# 80352201_Main_v4_1_1.net
KiCad netlist of a schematic drawn in Altium Designer
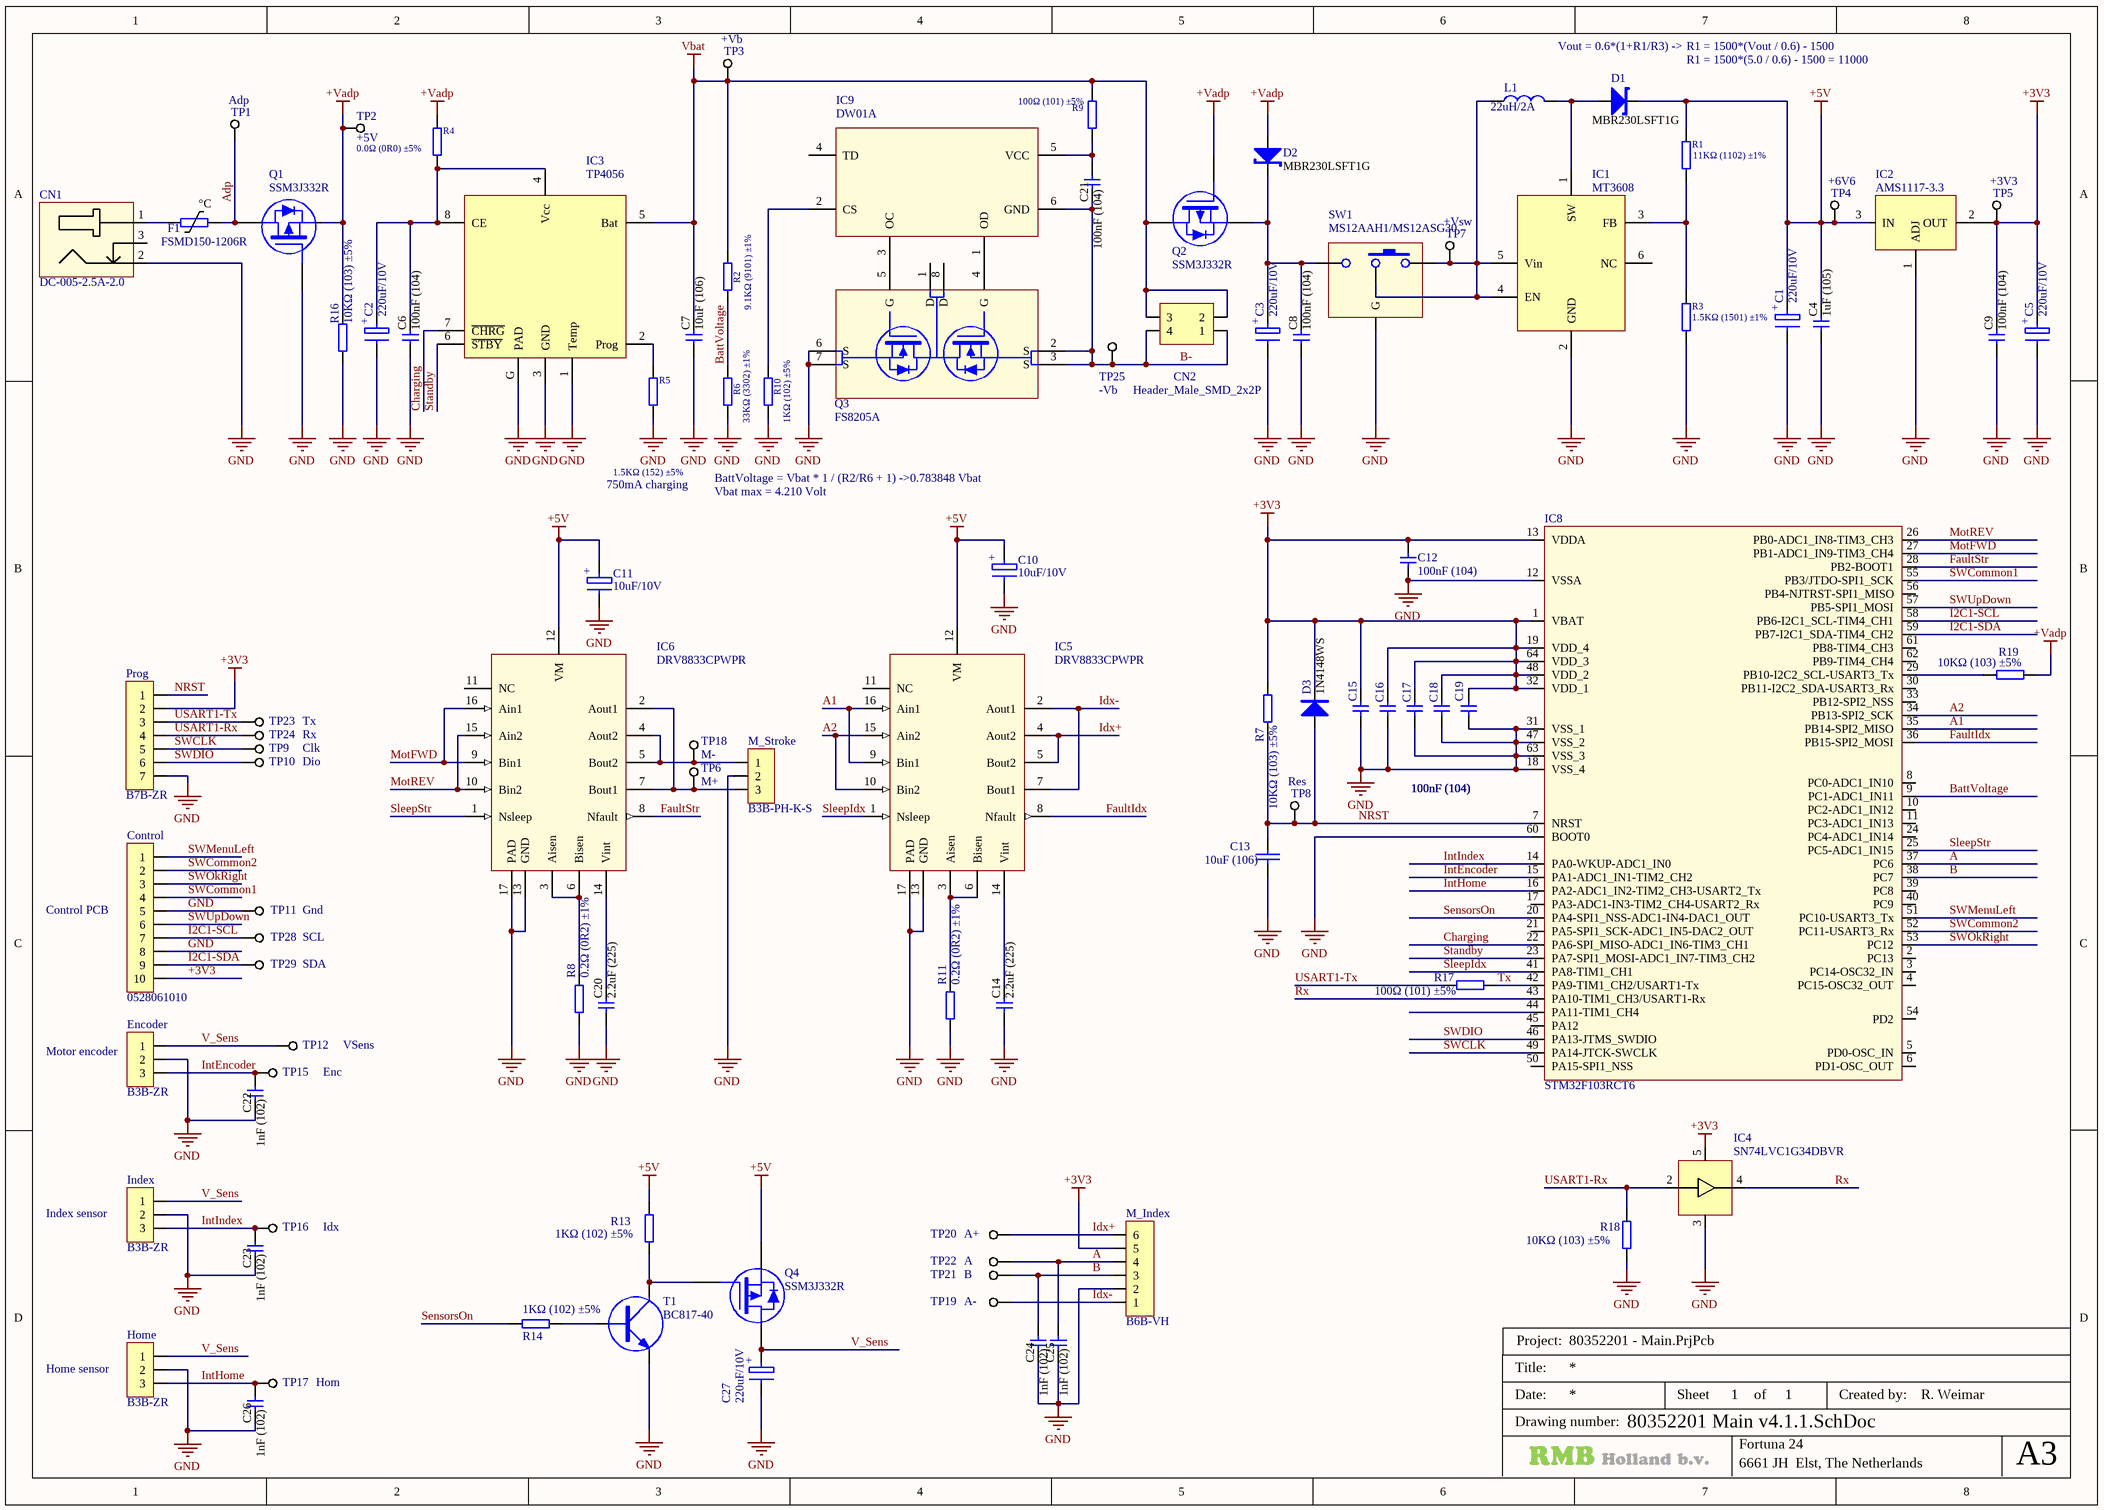
[diagram p0: 80352201 Main v4.1.1.SchDoc]

(export (version "E")
  (design (tool "Eeschema 10.0.6"))
  (components
    (comp (ref "C1")
      (value "220uF/10V")
      (footprint "C/CAP_POL_6032-28")
      (description "CapacitorPol")
      (libsource (lib "ReneWeimar") (part "C/CAP_Pol"))
    )
    (comp (ref "C2")
      (value "220uF/10V")
      (footprint "C/CAP_POL_6032-28")
      (description "CapacitorPol")
      (libsource (lib "ReneWeimar") (part "C/CAP_Pol"))
    )
    (comp (ref "C3")
      (value "220uF/10V")
      (footprint "C/CAP_POL_6032-28")
      (description "CapacitorPol")
      (libsource (lib "ReneWeimar") (part "C/CAP_Pol"))
    )
    (comp (ref "C4")
      (value "1uF (105)")
      (footprint "C/0603/H")
      (description "Capacitor")
      (libsource (lib "ReneWeimar") (part "CAP"))
    )
    (comp (ref "C5")
      (value "220uF/10V")
      (footprint "C/CAP_POL_6032-28")
      (description "CapacitorPol")
      (libsource (lib "ReneWeimar") (part "C/CAP_Pol"))
    )
    (comp (ref "C6")
      (value "100nF (104)")
      (footprint "C/0603/H")
      (description "Capacitor")
      (libsource (lib "ReneWeimar") (part "CAP"))
    )
    (comp (ref "C7")
      (value "10uF (106)")
      (footprint "C/0603/H")
      (description "Capacitor")
      (libsource (lib "ReneWeimar") (part "CAP"))
    )
    (comp (ref "C8")
      (value "100nF (104)")
      (footprint "C/0603/H")
      (description "Capacitor")
      (libsource (lib "ReneWeimar") (part "CAP"))
    )
    (comp (ref "C9")
      (value "100nF (104)")
      (footprint "C/0603/H")
      (description "Capacitor")
      (libsource (lib "ReneWeimar") (part "CAP"))
    )
    (comp (ref "C10")
      (value "10uF/10V")
      (footprint "C/CAP_POL_3216-18")
      (description "CapacitorPol")
      (libsource (lib "ReneWeimar") (part "C/CAP_Pol"))
    )
    (comp (ref "C11")
      (value "10uF/10V")
      (footprint "C/CAP_POL_3216-18")
      (description "CapacitorPol")
      (libsource (lib "ReneWeimar") (part "C/CAP_Pol"))
    )
    (comp (ref "C12")
      (value "100nF (104)")
      (footprint "C/0603/H")
      (description "Capacitor non polarized")
      (fields (field (name "MANUFACTURER") "Generic") (field (name "TOLERANCE") "10%"))
      (libsource (lib "80432001 - UI V0") (part "Capacitor non polarized"))
    )
    (comp (ref "C13")
      (value "10uF (106)")
      (footprint "C/0603/H")
      (description "Capacitor")
      (libsource (lib "") (part "CAP_1"))
    )
    (comp (ref "C14")
      (value "2.2uF (225)")
      (footprint "C/0603/H")
      (description "Capacitor")
      (libsource (lib "ReneWeimar") (part "CAP"))
    )
    (comp (ref "C15")
      (value "100nF (104)")
      (footprint "C/0603/H")
      (description "Capacitor")
      (libsource (lib "80432001 - UI V0") (part "CAP"))
    )
    (comp (ref "C16")
      (value "100nF (104)")
      (footprint "C/0603/H")
      (description "Capacitor non polarized")
      (fields (field (name "MANUFACTURER") "Generic") (field (name "TOLERANCE") "10%"))
      (libsource (lib "80432001 - UI V0") (part "Capacitor non polarized"))
    )
    (comp (ref "C17")
      (value "100nF (104)")
      (footprint "C/0603/H")
      (description "Capacitor")
      (libsource (lib "80432001 - UI V0") (part "CAP"))
    )
    (comp (ref "C18")
      (value "100nF (104)")
      (footprint "C/0603/H")
      (description "Capacitor")
      (libsource (lib "80432001 - UI V0") (part "CAP"))
    )
    (comp (ref "C19")
      (value "100nF (104)")
      (footprint "C/0603/H")
      (description "Capacitor non polarized")
      (fields (field (name "MANUFACTURER") "Generic") (field (name "TOLERANCE") "10%"))
      (libsource (lib "80432001 - UI V0") (part "Capacitor non polarized"))
    )
    (comp (ref "C20")
      (value "2.2uF (225)")
      (footprint "C/0603/H")
      (description "Capacitor")
      (libsource (lib "ReneWeimar") (part "CAP"))
    )
    (comp (ref "C21")
      (value "100nF (104)")
      (footprint "C/0603/H")
      (description "Capacitor")
      (libsource (lib "ReneWeimar") (part "CAP"))
    )
    (comp (ref "C22")
      (value "1nF (102)")
      (footprint "C/0603/H")
      (description "Capacitor")
      (libsource (lib "ReneWeimar") (part "CAP"))
    )
    (comp (ref "C23")
      (value "1nF (102)")
      (footprint "C/0603/H")
      (description "Capacitor")
      (libsource (lib "ReneWeimar") (part "CAP"))
    )
    (comp (ref "C24")
      (value "1nF (102)")
      (footprint "C/0603/H")
      (description "Capacitor")
      (libsource (lib "ReneWeimar") (part "CAP"))
    )
    (comp (ref "C25")
      (value "1nF (102)")
      (footprint "C/0603/H")
      (description "Capacitor")
      (libsource (lib "ReneWeimar") (part "CAP"))
    )
    (comp (ref "C26")
      (value "1nF (102)")
      (footprint "C/0603/H")
      (description "Capacitor")
      (libsource (lib "ReneWeimar") (part "CAP"))
    )
    (comp (ref "C27")
      (value "220uF/10V")
      (footprint "C/CAP_POL_6032-28")
      (description "CapacitorPol")
      (libsource (lib "ReneWeimar") (part "C/CAP_Pol"))
    )
    (comp (ref "CN1")
      (value "DC-005-2.5A-2.0")
      (footprint "DC-005-2.5A-2.5")
      (description "XKB_DC-005-2.5A-2.0_Power jack")
      (libsource (lib "ReneWeimar") (part "DC_Power_Jack"))
    )
    (comp (ref "CN2")
      (value "Header_Male_SMD_2x2P")
      (footprint "Header2x2P_L10")
      (description "Connector")
      (libsource (lib "ReneWeimar") (part "CON2*2"))
    )
    (comp (ref "Control")
      (value "0528061010")
      (footprint "FPC_1.0-10P_Straight")
      (description "Molex_0528061010_FPC 1.0 10P Connector")
      (libsource (lib "ReneWeimar") (part "CON10"))
    )
    (comp (ref "D1")
      (value "MBR230LSFT1G")
      (footprint "SOD123LF")
      (description "Diode")
      (libsource (lib "ReneWeimar") (part "DIODE_SHOTTKY"))
    )
    (comp (ref "D2")
      (value "MBR230LSFT1G")
      (footprint "SOD123LF")
      (description "ON semiconductor_MBR230LSFT1G_Diode")
      (libsource (lib "ReneWeimar") (part "DIODE_SHOTTKY"))
    )
    (comp (ref "D3")
      (value "1N4148WS")
      (footprint "SOD123")
      (description "Diode")
      (libsource (lib "ReneWeimar") (part "DIODE"))
    )
    (comp (ref "Encoder")
      (value "B3B-ZR")
      (footprint "B3B-ZR")
      (description "Connector")
      (libsource (lib "ReneWeimar") (part "CON3"))
    )
    (comp (ref "F1")
      (value "FSMD150-1206R")
      (footprint "F/1206R_PTC")
      (description "Fuzetec PTC fuse 2.5 A 16V")
      (libsource (lib "ReneWeimar") (part "PTC"))
    )
    (comp (ref "Home")
      (value "B3B-ZR")
      (footprint "B3B-ZR")
      (description "Connector")
      (libsource (lib "ReneWeimar") (part "CON3"))
    )
    (comp (ref "IC1")
      (value "MT3608")
      (footprint "IC/SOT23-6L")
      (description "Aerosemi_MT3608_Boost converter")
      (libsource (lib "ReneWeimar") (part "IC/MT3608"))
    )
    (comp (ref "IC2")
      (value "AMS1117-3.3")
      (footprint "SOT223/Rest")
      (description "AMS_AMS1117-3.3_Voltage regulator")
      (libsource (lib "ReneWeimar") (part "IC/ASM1117-SOT223"))
    )
    (comp (ref "IC3")
      (value "TP4056")
      (footprint "HSOP-8")
      (description "Top power_TP4056-42-SOP8-PP_18650 charger")
      (libsource (lib "ReneWeimar") (part "IC/TP4056"))
    )
    (comp (ref "IC4")
      (value "SN74LVC1G34DBVR")
      (footprint "SOT753")
      (description "Bus buffer")
      (libsource (lib "ReneWeimar") (part "LogicLevelShifter"))
    )
    (comp (ref "IC5")
      (value "DRV8833CPWPR")
      (footprint "HTSSOP16")
      (description "TI_DRV8833CPWPR_DC/Stepper motor driver")
      (libsource (lib "ReneWeimar") (part "IC/DRV8833CPWPR"))
    )
    (comp (ref "IC6")
      (value "DRV8833CPWPR")
      (footprint "HTSSOP16")
      (description "TI_DRV8833CPWPR_DC/Stepper motor driver")
      (libsource (lib "ReneWeimar") (part "IC/DRV8833CPWPR"))
    )
    (comp (ref "IC8")
      (value "STM32F103RCT6")
      (footprint "LQFP64")
      (description "ST_STM32F103RCT6_Microprocessor")
      (libsource (lib "ReneWeimar") (part "IC/STM32F100RBT6"))
    )
    (comp (ref "IC9")
      (value "DW01A")
      (footprint "IC/SOT23-6L")
      (description "Protection circuit")
      (libsource (lib "ReneWeimar") (part "IC/DW01A"))
    )
    (comp (ref "Index")
      (value "B3B-ZR")
      (footprint "B3B-ZR")
      (description "Connector")
      (libsource (lib "ReneWeimar") (part "CON3"))
    )
    (comp (ref "L1")
      (value "22uH/2A")
      (footprint "Coil12x12")
      (description "INDUCTOR")
      (libsource (lib "ReneWeimar") (part "INDUCTOR1"))
    )
    (comp (ref "M_Index")
      (value "B6B-VH")
      (footprint "B6B-ZR")
      (description "Connector")
      (libsource (lib "ReneWeimar") (part "CON6"))
    )
    (comp (ref "M_Stroke")
      (value "B3B-PH-K-S")
      (footprint "B3B-PH-KL")
      (description "Connector")
      (libsource (lib "") (part "CON3_1"))
    )
    (comp (ref "Prog")
      (value "B7B-ZR")
      (footprint "B7B-ZR")
      (description "Connector")
      (libsource (lib "ReneWeimar") (part "CON7"))
    )
    (comp (ref "Q1")
      (value "SSM3J332R")
      (footprint "SOT23-F")
      (description "Toshiba_SSM3J332R_P-Channel MOSFET")
      (libsource (lib "ReneWeimar") (part "MOSFET-P-CHANNEL"))
    )
    (comp (ref "Q2")
      (value "SSM3J332R")
      (footprint "SOT23-F")
      (description "N-Channel MOSFET")
      (libsource (lib "ReneWeimar") (part "MOSFET-P-CHANNEL"))
    )
    (comp (ref "Q3")
      (value "FS8205A")
      (footprint "TSSOP-8")
      (description "N-P-Channel MOSFET")
      (libsource (lib "ReneWeimar") (part "MOSFET-N-P-DUAL"))
    )
    (comp (ref "Q4")
      (value "SSM3J332R")
      (footprint "SOT23-F")
      (description "P-Channel MOSFET")
      (libsource (lib "ReneWeimar") (part "MOSFET-P-CHANNEL"))
    )
    (comp (ref "R1")
      (value "11KΩ (1102) ±1%")
      (footprint "r/0603/H")
      (description "Resistor")
      (libsource (lib "ReneWeimar") (part "RES"))
    )
    (comp (ref "R2")
      (value "9.1KΩ (9101) ±1%")
      (footprint "r/0603/H")
      (description "Resistor")
      (libsource (lib "ReneWeimar") (part "RES"))
    )
    (comp (ref "R3")
      (value "1.5KΩ (1501) ±1%")
      (footprint "r/0603/H")
      (description "Resistor")
      (libsource (lib "ReneWeimar") (part "RES"))
    )
    (comp (ref "R4")
      (value "0.0Ω (0R0) ±5%")
      (footprint "R/1206/b")
      (description "Resistor")
      (libsource (lib "ReneWeimar") (part "RES"))
    )
    (comp (ref "R5")
      (value "1.5KΩ (152) ±5%")
      (footprint "r/0603/H")
      (description "Resistor")
      (libsource (lib "ReneWeimar") (part "RES"))
    )
    (comp (ref "R6")
      (value "33KΩ (3302) ±1%")
      (footprint "r/0603/H")
      (description "Resistor")
      (libsource (lib "ReneWeimar") (part "RES"))
    )
    (comp (ref "R7")
      (value "10KΩ (103) ±5%")
      (footprint "r/0603/H")
      (libsource (lib "ReneWeimar") (part "RES"))
    )
    (comp (ref "R8")
      (value "0.2Ω (0R2) ±1%")
      (footprint "R/2512")
      (libsource (lib "ReneWeimar") (part "RES"))
    )
    (comp (ref "R9")
      (value "100Ω (101) ±5%")
      (footprint "r/0603/H")
      (description "Resistor")
      (libsource (lib "ReneWeimar") (part "RES"))
    )
    (comp (ref "R10")
      (value "1KΩ (102) ±5%")
      (footprint "r/0603/H")
      (description "Resistor")
      (libsource (lib "ReneWeimar") (part "RES"))
    )
    (comp (ref "R11")
      (value "0.2Ω (0R2) ±1%")
      (footprint "R/2512")
      (libsource (lib "ReneWeimar") (part "RES"))
    )
    (comp (ref "R13")
      (value "1KΩ (102) ±5%")
      (footprint "r/0603/H")
      (description "Resistor")
      (libsource (lib "ReneWeimar") (part "RES"))
    )
    (comp (ref "R14")
      (value "1KΩ (102) ±5%")
      (footprint "r/0603/H")
      (description "Resistor")
      (libsource (lib "ReneWeimar") (part "RES"))
    )
    (comp (ref "R16")
      (value "10KΩ (103) ±5%")
      (footprint "r/0603/H")
      (libsource (lib "ReneWeimar") (part "RES"))
    )
    (comp (ref "R17")
      (value "100Ω (101) ±5%")
      (footprint "r/0603/H")
      (description "Resistor")
      (libsource (lib "ReneWeimar") (part "RES"))
    )
    (comp (ref "R18")
      (value "10KΩ (103) ±5%")
      (footprint "r/0603/H")
      (description "Resistor")
      (libsource (lib "ReneWeimar") (part "RES"))
    )
    (comp (ref "R19")
      (value "10KΩ (103) ±5%")
      (footprint "r/0603/H")
      (description "Resistor")
      (libsource (lib "ReneWeimar") (part "RES"))
    )
    (comp (ref "SW1")
      (value "MS12AAH1/MS12ASG30")
      (footprint "NKK_MS12AAH1")
      (description "NKK_MS12AAH1/MS12ASG30_Slide switch")
      (libsource (lib "ReneWeimar") (part "SW-SPDT"))
    )
    (comp (ref "T1")
      (value "BC817-40")
      (footprint "T/NPN/TO23")
      (description "Transistor NPN")
      (libsource (lib "ReneWeimar") (part "T/NPN"))
    )
    (comp (ref "TP1")
      (value "Adp")
      (footprint "TestPoint1.2")
      (libsource (lib "ReneWeimar") (part "TestPoint"))
    )
    (comp (ref "TP2")
      (value "+5V")
      (footprint "TestPoint1.2")
      (libsource (lib "ReneWeimar") (part "TestPoint"))
    )
    (comp (ref "TP3")
      (value "+Vb")
      (footprint "TestPoint1.2")
      (libsource (lib "ReneWeimar") (part "TestPoint"))
    )
    (comp (ref "TP4")
      (value "+6V6")
      (footprint "TestPoint1.2")
      (libsource (lib "ReneWeimar") (part "TestPoint"))
    )
    (comp (ref "TP5")
      (value "+3V3")
      (footprint "TestPoint1.2")
      (libsource (lib "ReneWeimar") (part "TestPoint"))
    )
    (comp (ref "TP6")
      (value "M+")
      (footprint "TestPoint1.2")
      (libsource (lib "ReneWeimar") (part "TestPoint"))
    )
    (comp (ref "TP7")
      (value "+Vsw")
      (footprint "TestPoint1.2")
      (libsource (lib "ReneWeimar") (part "TestPoint"))
    )
    (comp (ref "TP8")
      (value "Res")
      (footprint "TestPoint1.2")
      (libsource (lib "ReneWeimar") (part "TestPoint"))
    )
    (comp (ref "TP9")
      (value "Clk")
      (footprint "TestPoint1.2")
      (libsource (lib "ReneWeimar") (part "TestPoint"))
    )
    (comp (ref "TP10")
      (value "Dio")
      (footprint "TestPoint1.2")
      (libsource (lib "ReneWeimar") (part "TestPoint"))
    )
    (comp (ref "TP11")
      (value "Gnd")
      (footprint "TestPoint1.2")
      (libsource (lib "ReneWeimar") (part "TestPoint"))
    )
    (comp (ref "TP12")
      (value "VSens")
      (footprint "TestPoint1.2")
      (libsource (lib "ReneWeimar") (part "TestPoint"))
    )
    (comp (ref "TP15")
      (value "Enc")
      (footprint "TestPoint1.2")
      (libsource (lib "ReneWeimar") (part "TestPoint"))
    )
    (comp (ref "TP16")
      (value "Idx")
      (footprint "TestPoint1.2")
      (libsource (lib "ReneWeimar") (part "TestPoint"))
    )
    (comp (ref "TP17")
      (value "Hom")
      (footprint "TestPoint1.2")
      (libsource (lib "ReneWeimar") (part "TestPoint"))
    )
    (comp (ref "TP18")
      (value "M-")
      (footprint "TestPoint1.2")
      (libsource (lib "ReneWeimar") (part "TestPoint"))
    )
    (comp (ref "TP19")
      (value "A-")
      (footprint "TestPoint1.2")
      (libsource (lib "ReneWeimar") (part "TestPoint"))
    )
    (comp (ref "TP20")
      (value "A+")
      (footprint "TestPoint1.2")
      (libsource (lib "ReneWeimar") (part "TestPoint"))
    )
    (comp (ref "TP21")
      (value "B")
      (footprint "TestPoint1.2")
      (libsource (lib "ReneWeimar") (part "TestPoint"))
    )
    (comp (ref "TP22")
      (value "A")
      (footprint "TestPoint1.2")
      (libsource (lib "ReneWeimar") (part "TestPoint"))
    )
    (comp (ref "TP23")
      (value "Tx")
      (footprint "TestPoint1.2")
      (libsource (lib "ReneWeimar") (part "TestPoint"))
    )
    (comp (ref "TP24")
      (value "Rx")
      (footprint "TestPoint1.2")
      (libsource (lib "ReneWeimar") (part "TestPoint"))
    )
    (comp (ref "TP25")
      (value "-Vb")
      (footprint "TestPoint1.2")
      (libsource (lib "ReneWeimar") (part "TestPoint"))
    )
    (comp (ref "TP28")
      (value "SCL")
      (footprint "TestPoint1.2")
      (libsource (lib "ReneWeimar") (part "TestPoint"))
    )
    (comp (ref "TP29")
      (value "SDA")
      (footprint "TestPoint1.2")
      (libsource (lib "ReneWeimar") (part "TestPoint"))
    )
  )
  (nets
    (net (code "1") (name "+3V3") (class "Default")
      (node (ref "C12") (pin "1") (pintype "passive"))
      (node (ref "C15") (pin "1") (pinfunction "1_1") (pintype "passive"))
      (node (ref "C16") (pin "2") (pintype "passive"))
      (node (ref "C17") (pin "2") (pinfunction "2_2") (pintype "passive"))
      (node (ref "C18") (pin "2") (pinfunction "2_2") (pintype "passive"))
      (node (ref "C19") (pin "1") (pintype "passive"))
      (node (ref "C5") (pin "2") (pinfunction "2_2") (pintype "passive"))
      (node (ref "C9") (pin "1") (pinfunction "1_1") (pintype "passive"))
      (node (ref "Control") (pin "10") (pinfunction "10_10") (pintype "passive"))
      (node (ref "D3") (pin "K") (pinfunction "K_K") (pintype "passive"))
      (node (ref "IC2") (pin "2") (pinfunction "OUT_2") (pintype "passive"))
      (node (ref "IC4") (pin "5") (pinfunction "VCC_5") (pintype "passive"))
      (node (ref "IC8") (pin "1") (pinfunction "VBAT_1") (pintype "passive"))
      (node (ref "IC8") (pin "13") (pinfunction "VDDA_13") (pintype "passive"))
      (node (ref "IC8") (pin "19") (pinfunction "VDD_4_19") (pintype "passive"))
      (node (ref "IC8") (pin "32") (pinfunction "VDD_1_32") (pintype "passive"))
      (node (ref "IC8") (pin "48") (pinfunction "VDD_2_48") (pintype "passive"))
      (node (ref "IC8") (pin "64") (pinfunction "VDD_3_64") (pintype "passive"))
      (node (ref "M_Index") (pin "5") (pinfunction "5_5") (pintype "passive"))
      (node (ref "Prog") (pin "2") (pinfunction "2_2") (pintype "passive"))
      (node (ref "R7") (pin "2") (pinfunction "2_2") (pintype "passive"))
      (node (ref "TP5") (pin "1") (pinfunction "1_1") (pintype "passive"))
    )
    (net (code "2") (name "+5V") (class "Default")
      (node (ref "C1") (pin "2") (pinfunction "2_2") (pintype "passive"))
      (node (ref "C10") (pin "2") (pinfunction "2_2") (pintype "passive"))
      (node (ref "C11") (pin "2") (pinfunction "2_2") (pintype "passive"))
      (node (ref "C4") (pin "1") (pinfunction "1_1") (pintype "passive"))
      (node (ref "D1") (pin "K") (pinfunction "K_K") (pintype "passive"))
      (node (ref "IC2") (pin "3") (pinfunction "IN_3") (pintype "passive"))
      (node (ref "IC5") (pin "12") (pinfunction "VM_12") (pintype "power_in"))
      (node (ref "IC6") (pin "12") (pinfunction "VM_12") (pintype "power_in"))
      (node (ref "Q4") (pin "S") (pinfunction "S_S") (pintype "passive"))
      (node (ref "R1") (pin "2") (pinfunction "2_2") (pintype "passive"))
      (node (ref "R13") (pin "2") (pinfunction "2_2") (pintype "passive"))
      (node (ref "TP4") (pin "1") (pinfunction "1_1") (pintype "passive"))
    )
    (net (code "3") (name "+Vadp") (class "Default")
      (node (ref "D2") (pin "A") (pinfunction "A_A") (pintype "passive"))
      (node (ref "Q1") (pin "S") (pinfunction "S_S") (pintype "passive"))
      (node (ref "Q2") (pin "G") (pinfunction "G_G") (pintype "passive"))
      (node (ref "R16") (pin "2") (pinfunction "2_2") (pintype "passive"))
      (node (ref "R19") (pin "1") (pinfunction "1_1") (pintype "passive"))
      (node (ref "R4") (pin "2") (pinfunction "2_2") (pintype "passive"))
      (node (ref "TP2") (pin "1") (pinfunction "1_1") (pintype "passive"))
    )
    (net (code "4") (name "/A") (class "Default")
      (node (ref "C25") (pin "1") (pinfunction "1_1") (pintype "passive"))
      (node (ref "IC8") (pin "37") (pinfunction "PC6_37") (pintype "passive"))
      (node (ref "M_Index") (pin "4") (pinfunction "4_4") (pintype "passive"))
      (node (ref "TP22") (pin "1") (pinfunction "1_1") (pintype "passive"))
    )
    (net (code "5") (name "/A1") (class "Default")
      (node (ref "IC5") (pin "16") (pinfunction "Ain1_16") (pintype "input"))
      (node (ref "IC5") (pin "9") (pinfunction "Bin1_9") (pintype "input"))
      (node (ref "IC8") (pin "35") (pinfunction "PB14-SPI2_MISO_35") (pintype "passive"))
    )
    (net (code "6") (name "/A2") (class "Default")
      (node (ref "IC5") (pin "10") (pinfunction "Bin2_10") (pintype "input"))
      (node (ref "IC5") (pin "15") (pinfunction "Ain2_15") (pintype "input"))
      (node (ref "IC8") (pin "34") (pinfunction "PB13-SPI2_SCK_34") (pintype "passive"))
    )
    (net (code "7") (name "/Adp") (class "Default")
      (node (ref "F1") (pin "2") (pinfunction "2_2") (pintype "passive"))
      (node (ref "Q1") (pin "D") (pinfunction "D_D") (pintype "passive"))
      (node (ref "TP1") (pin "1") (pinfunction "1_1") (pintype "passive"))
    )
    (net (code "8") (name "/B") (class "Default")
      (node (ref "C24") (pin "1") (pinfunction "1_1") (pintype "passive"))
      (node (ref "IC8") (pin "38") (pinfunction "PC7_38") (pintype "passive"))
      (node (ref "M_Index") (pin "3") (pinfunction "3_3") (pintype "passive"))
      (node (ref "TP21") (pin "1") (pinfunction "1_1") (pintype "passive"))
    )
    (net (code "9") (name "/B-") (class "Default")
      (node (ref "C21") (pin "2") (pinfunction "2_2") (pintype "passive"))
      (node (ref "CN2") (pin "1") (pinfunction "1_1") (pintype "passive"))
      (node (ref "CN2") (pin "4") (pinfunction "4_4") (pintype "passive"))
      (node (ref "IC9") (pin "6") (pinfunction "GND_6") (pintype "passive"))
      (node (ref "Q3") (pin "2") (pinfunction "S_2") (pintype "passive"))
      (node (ref "Q3") (pin "3") (pinfunction "S_3") (pintype "passive"))
      (node (ref "TP25") (pin "1") (pinfunction "1_1") (pintype "passive"))
    )
    (net (code "10") (name "/BattVoltage") (class "Default")
      (node (ref "IC8") (pin "9") (pinfunction "PC1-ADC1_IN11_9") (pintype "passive"))
      (node (ref "R2") (pin "1") (pinfunction "1_1") (pintype "passive"))
      (node (ref "R6") (pin "2") (pinfunction "2_2") (pintype "passive"))
    )
    (net (code "11") (name "/Charging") (class "Default")
      (node (ref "IC3") (pin "7") (pinfunction "~{CHRG}_7") (pintype "passive"))
      (node (ref "IC8") (pin "22") (pinfunction "PA6-SPI_MISO-ADC1_IN6-TIM3_CH1_22") (pintype "passive"))
    )
    (net (code "12") (name "/FaultIdx") (class "Default")
      (node (ref "IC5") (pin "8") (pinfunction "Nfault_8") (pintype "output"))
      (node (ref "IC8") (pin "36") (pinfunction "PB15-SPI2_MOSI_36") (pintype "passive"))
    )
    (net (code "13") (name "/FaultStr") (class "Default")
      (node (ref "IC6") (pin "8") (pinfunction "Nfault_8") (pintype "output"))
      (node (ref "IC8") (pin "28") (pinfunction "PB2-BOOT1_28") (pintype "passive"))
    )
    (net (code "14") (name "/I2C1-SCL") (class "Default")
      (node (ref "Control") (pin "7") (pinfunction "7_7") (pintype "passive"))
      (node (ref "IC8") (pin "58") (pinfunction "PB6-I2C1_SCL-TIM4_CH1_58") (pintype "passive"))
      (node (ref "TP28") (pin "1") (pinfunction "1_1") (pintype "passive"))
    )
    (net (code "15") (name "/I2C1-SDA") (class "Default")
      (node (ref "Control") (pin "9") (pinfunction "9_9") (pintype "passive"))
      (node (ref "IC8") (pin "59") (pinfunction "PB7-I2C1_SDA-TIM4_CH2_59") (pintype "passive"))
      (node (ref "TP29") (pin "1") (pinfunction "1_1") (pintype "passive"))
    )
    (net (code "16") (name "/Idx+") (class "Default")
      (node (ref "IC5") (pin "4") (pinfunction "Aout2_4") (pintype "passive"))
      (node (ref "IC5") (pin "5") (pinfunction "Bout2_5") (pintype "passive"))
      (node (ref "M_Index") (pin "6") (pinfunction "6_6") (pintype "passive"))
      (node (ref "TP20") (pin "1") (pinfunction "1_1") (pintype "passive"))
    )
    (net (code "17") (name "/Idx-") (class "Default")
      (node (ref "IC5") (pin "2") (pinfunction "Aout1_2") (pintype "passive"))
      (node (ref "IC5") (pin "7") (pinfunction "Bout1_7") (pintype "passive"))
      (node (ref "M_Index") (pin "1") (pinfunction "1_1") (pintype "passive"))
      (node (ref "TP19") (pin "1") (pinfunction "1_1") (pintype "passive"))
    )
    (net (code "18") (name "/IntEncoder") (class "Default")
      (node (ref "C22") (pin "1") (pinfunction "1_1") (pintype "passive"))
      (node (ref "Encoder") (pin "3") (pinfunction "3_3") (pintype "passive"))
      (node (ref "IC8") (pin "15") (pinfunction "PA1-ADC1_IN1-TIM2_CH2_15") (pintype "passive"))
      (node (ref "TP15") (pin "1") (pinfunction "1_1") (pintype "passive"))
    )
    (net (code "19") (name "/IntHome") (class "Default")
      (node (ref "C26") (pin "1") (pinfunction "1_1") (pintype "passive"))
      (node (ref "Home") (pin "3") (pinfunction "3_3") (pintype "passive"))
      (node (ref "IC8") (pin "16") (pinfunction "PA2-ADC1_IN2-TIM2_CH3-USART2_Tx_16") (pintype "passive"))
      (node (ref "TP17") (pin "1") (pinfunction "1_1") (pintype "passive"))
    )
    (net (code "20") (name "/IntIndex") (class "Default")
      (node (ref "C23") (pin "1") (pinfunction "1_1") (pintype "passive"))
      (node (ref "IC8") (pin "14") (pinfunction "PA0-WKUP-ADC1_IN0_14") (pintype "passive"))
      (node (ref "Index") (pin "3") (pinfunction "3_3") (pintype "passive"))
      (node (ref "TP16") (pin "1") (pinfunction "1_1") (pintype "passive"))
    )
    (net (code "21") (name "/MotFWD") (class "Default")
      (node (ref "IC6") (pin "16") (pinfunction "Ain1_16") (pintype "input"))
      (node (ref "IC6") (pin "9") (pinfunction "Bin1_9") (pintype "input"))
      (node (ref "IC8") (pin "27") (pinfunction "PB1-ADC1_IN9-TIM3_CH4_27") (pintype "passive"))
    )
    (net (code "22") (name "/MotREV") (class "Default")
      (node (ref "IC6") (pin "10") (pinfunction "Bin2_10") (pintype "input"))
      (node (ref "IC6") (pin "15") (pinfunction "Ain2_15") (pintype "input"))
      (node (ref "IC8") (pin "26") (pinfunction "PB0-ADC1_IN8-TIM3_CH3_26") (pintype "passive"))
    )
    (net (code "23") (name "/NRST") (class "Default")
      (node (ref "C13") (pin "1") (pinfunction "1_1") (pintype "passive"))
      (node (ref "D3") (pin "A") (pinfunction "A_A") (pintype "passive"))
      (node (ref "IC8") (pin "7") (pinfunction "NRST_7") (pintype "passive"))
      (node (ref "Prog") (pin "1") (pinfunction "1_1") (pintype "passive"))
      (node (ref "R7") (pin "1") (pinfunction "1_1") (pintype "passive"))
      (node (ref "TP8") (pin "1") (pinfunction "1_1") (pintype "passive"))
    )
    (net (code "24") (name "/Rx") (class "Default")
      (node (ref "IC4") (pin "4") (pinfunction "Y_4") (pintype "passive"))
      (node (ref "IC8") (pin "43") (pinfunction "PA10-TIM1_CH3/USART1-Rx_43") (pintype "passive"))
    )
    (net (code "25") (name "/SWCLK") (class "Default")
      (node (ref "IC8") (pin "49") (pinfunction "PA14-JTCK-SWCLK_49") (pintype "passive"))
      (node (ref "Prog") (pin "5") (pinfunction "5_5") (pintype "passive"))
      (node (ref "TP9") (pin "1") (pinfunction "1_1") (pintype "passive"))
    )
    (net (code "26") (name "/SWCommon1") (class "Default")
      (node (ref "Control") (pin "4") (pinfunction "4_4") (pintype "passive"))
      (node (ref "IC8") (pin "55") (pinfunction "PB3/JTDO-SPI1_SCK_55") (pintype "passive"))
    )
    (net (code "27") (name "/SWCommon2") (class "Default")
      (node (ref "Control") (pin "2") (pinfunction "2_2") (pintype "passive"))
      (node (ref "IC8") (pin "52") (pinfunction "PC11-USART3_Rx_52") (pintype "passive"))
    )
    (net (code "28") (name "/SWDIO") (class "Default")
      (node (ref "IC8") (pin "46") (pinfunction "PA13-JTMS_SWDIO_46") (pintype "passive"))
      (node (ref "Prog") (pin "6") (pinfunction "6_6") (pintype "passive"))
      (node (ref "TP10") (pin "1") (pinfunction "1_1") (pintype "passive"))
    )
    (net (code "29") (name "/SWMenuLeft") (class "Default")
      (node (ref "Control") (pin "1") (pinfunction "1_1") (pintype "passive"))
      (node (ref "IC8") (pin "51") (pinfunction "PC10-USART3_Tx_51") (pintype "passive"))
    )
    (net (code "30") (name "/SWOkRight") (class "Default")
      (node (ref "Control") (pin "3") (pinfunction "3_3") (pintype "passive"))
      (node (ref "IC8") (pin "53") (pinfunction "PC12_53") (pintype "passive"))
    )
    (net (code "31") (name "/SWUpDown") (class "Default")
      (node (ref "Control") (pin "6") (pinfunction "6_6") (pintype "passive"))
      (node (ref "IC8") (pin "57") (pinfunction "PB5-SPI1_MOSI_57") (pintype "passive"))
    )
    (net (code "32") (name "/SensorsOn") (class "Default")
      (node (ref "IC8") (pin "20") (pinfunction "PA4-SPI1_NSS-ADC1-IN4-DAC1_OUT_20") (pintype "passive"))
      (node (ref "R14") (pin "1") (pinfunction "1_1") (pintype "passive"))
    )
    (net (code "33") (name "/SleepIdx") (class "Default")
      (node (ref "IC5") (pin "1") (pinfunction "Nsleep_1") (pintype "input"))
      (node (ref "IC8") (pin "41") (pinfunction "PA8-TIM1_CH1_41") (pintype "passive"))
    )
    (net (code "34") (name "/SleepStr") (class "Default")
      (node (ref "IC6") (pin "1") (pinfunction "Nsleep_1") (pintype "input"))
      (node (ref "IC8") (pin "25") (pinfunction "PC5-ADC1_IN15_25") (pintype "passive"))
    )
    (net (code "35") (name "/Standby") (class "Default")
      (node (ref "IC3") (pin "6") (pinfunction "~{STBY}_6") (pintype "passive"))
      (node (ref "IC8") (pin "23") (pinfunction "PA7-SPI1_MOSI-ADC1_IN7-TIM3_CH2_23") (pintype "passive"))
    )
    (net (code "36") (name "/Tx") (class "Default")
      (node (ref "IC8") (pin "42") (pinfunction "PA9-TIM1_CH2/USART1-Tx_42") (pintype "passive"))
      (node (ref "R17") (pin "1") (pinfunction "1_1") (pintype "passive"))
    )
    (net (code "37") (name "/USART1-Rx") (class "Default")
      (node (ref "IC4") (pin "2") (pinfunction "A_2") (pintype "passive"))
      (node (ref "Prog") (pin "4") (pinfunction "4_4") (pintype "passive"))
      (node (ref "R18") (pin "1") (pinfunction "1_1") (pintype "passive"))
      (node (ref "TP24") (pin "1") (pinfunction "1_1") (pintype "passive"))
    )
    (net (code "38") (name "/USART1-Tx") (class "Default")
      (node (ref "Prog") (pin "3") (pinfunction "3_3") (pintype "passive"))
      (node (ref "R17") (pin "2") (pinfunction "2_2") (pintype "passive"))
      (node (ref "TP23") (pin "1") (pinfunction "1_1") (pintype "passive"))
    )
    (net (code "39") (name "/V_Sens") (class "Default")
      (node (ref "C27") (pin "2") (pinfunction "2_2") (pintype "passive"))
      (node (ref "Encoder") (pin "1") (pinfunction "1_1") (pintype "passive"))
      (node (ref "Home") (pin "1") (pinfunction "1_1") (pintype "passive"))
      (node (ref "Index") (pin "1") (pinfunction "1_1") (pintype "passive"))
      (node (ref "Q4") (pin "D") (pinfunction "D_D") (pintype "passive"))
      (node (ref "TP12") (pin "1") (pinfunction "1_1") (pintype "passive"))
    )
    (net (code "40") (name "GND") (class "Default")
      (node (ref "C1") (pin "1") (pinfunction "1_1") (pintype "passive"))
      (node (ref "C10") (pin "1") (pinfunction "1_1") (pintype "passive"))
      (node (ref "C11") (pin "1") (pinfunction "1_1") (pintype "passive"))
      (node (ref "C12") (pin "2") (pintype "passive"))
      (node (ref "C13") (pin "2") (pinfunction "2_2") (pintype "passive"))
      (node (ref "C14") (pin "2") (pinfunction "2_2") (pintype "passive"))
      (node (ref "C15") (pin "2") (pinfunction "2_2") (pintype "passive"))
      (node (ref "C16") (pin "1") (pintype "passive"))
      (node (ref "C17") (pin "1") (pinfunction "1_1") (pintype "passive"))
      (node (ref "C18") (pin "1") (pinfunction "1_1") (pintype "passive"))
      (node (ref "C19") (pin "2") (pintype "passive"))
      (node (ref "C2") (pin "1") (pinfunction "1_1") (pintype "passive"))
      (node (ref "C20") (pin "2") (pinfunction "2_2") (pintype "passive"))
      (node (ref "C22") (pin "2") (pinfunction "2_2") (pintype "passive"))
      (node (ref "C23") (pin "2") (pinfunction "2_2") (pintype "passive"))
      (node (ref "C24") (pin "2") (pinfunction "2_2") (pintype "passive"))
      (node (ref "C25") (pin "2") (pinfunction "2_2") (pintype "passive"))
      (node (ref "C26") (pin "2") (pinfunction "2_2") (pintype "passive"))
      (node (ref "C27") (pin "1") (pinfunction "1_1") (pintype "passive"))
      (node (ref "C3") (pin "1") (pinfunction "1_1") (pintype "passive"))
      (node (ref "C4") (pin "2") (pinfunction "2_2") (pintype "passive"))
      (node (ref "C5") (pin "1") (pinfunction "1_1") (pintype "passive"))
      (node (ref "C6") (pin "2") (pinfunction "2_2") (pintype "passive"))
      (node (ref "C7") (pin "2") (pinfunction "2_2") (pintype "passive"))
      (node (ref "C8") (pin "2") (pinfunction "2_2") (pintype "passive"))
      (node (ref "C9") (pin "2") (pinfunction "2_2") (pintype "passive"))
      (node (ref "CN1") (pin "2") (pinfunction "2_2") (pintype "passive"))
      (node (ref "Control") (pin "5") (pinfunction "5_5") (pintype "passive"))
      (node (ref "Control") (pin "8") (pinfunction "8_8") (pintype "passive"))
      (node (ref "Encoder") (pin "2") (pinfunction "2_2") (pintype "passive"))
      (node (ref "Home") (pin "2") (pinfunction "2_2") (pintype "passive"))
      (node (ref "IC1") (pin "2") (pinfunction "GND_2") (pintype "passive"))
      (node (ref "IC2") (pin "1") (pinfunction "ADJ_1") (pintype "passive"))
      (node (ref "IC3") (pin "1") (pinfunction "Temp_1") (pintype "passive"))
      (node (ref "IC3") (pin "3") (pinfunction "GND_3") (pintype "passive"))
      (node (ref "IC3") (pin "G") (pinfunction "PAD_G") (pintype "passive"))
      (node (ref "IC4") (pin "3") (pinfunction "GND_3") (pintype "passive"))
      (node (ref "IC5") (pin "13") (pinfunction "GND_13") (pintype "power_in"))
      (node (ref "IC5") (pin "17") (pinfunction "PAD_17") (pintype "power_in"))
      (node (ref "IC6") (pin "13") (pinfunction "GND_13") (pintype "power_in"))
      (node (ref "IC6") (pin "17") (pinfunction "PAD_17") (pintype "power_in"))
      (node (ref "IC8") (pin "12") (pinfunction "VSSA_12") (pintype "passive"))
      (node (ref "IC8") (pin "18") (pinfunction "VSS_4_18") (pintype "passive"))
      (node (ref "IC8") (pin "31") (pinfunction "VSS_1_31") (pintype "passive"))
      (node (ref "IC8") (pin "47") (pinfunction "VSS_2_47") (pintype "passive"))
      (node (ref "IC8") (pin "60") (pinfunction "BOOT0_60") (pintype "passive"))
      (node (ref "IC8") (pin "63") (pinfunction "VSS_3_63") (pintype "passive"))
      (node (ref "Index") (pin "2") (pinfunction "2_2") (pintype "passive"))
      (node (ref "M_Index") (pin "2") (pinfunction "2_2") (pintype "passive"))
      (node (ref "M_Stroke") (pin "2") (pinfunction "2_2") (pintype "passive"))
      (node (ref "Prog") (pin "7") (pinfunction "7_7") (pintype "passive"))
      (node (ref "Q1") (pin "G") (pinfunction "G_G") (pintype "passive"))
      (node (ref "Q3") (pin "6") (pinfunction "S_6") (pintype "passive"))
      (node (ref "Q3") (pin "7") (pinfunction "S_7") (pintype "passive"))
      (node (ref "R10") (pin "1") (pinfunction "1_1") (pintype "passive"))
      (node (ref "R11") (pin "1") (pinfunction "1_1") (pintype "passive"))
      (node (ref "R16") (pin "1") (pinfunction "1_1") (pintype "passive"))
      (node (ref "R18") (pin "2") (pinfunction "2_2") (pintype "passive"))
      (node (ref "R3") (pin "1") (pinfunction "1_1") (pintype "passive"))
      (node (ref "R5") (pin "1") (pinfunction "1_1") (pintype "passive"))
      (node (ref "R6") (pin "1") (pinfunction "1_1") (pintype "passive"))
      (node (ref "R8") (pin "1") (pinfunction "1_1") (pintype "passive"))
      (node (ref "SW1") (pin "G") (pinfunction "G_G") (pintype "passive"))
      (node (ref "T1") (pin "E") (pinfunction "E_E") (pintype "passive"))
      (node (ref "TP11") (pin "1") (pinfunction "1_1") (pintype "passive"))
    )
    (net (code "41") (name "Net-(C3-Pad2)") (class "Default")
      (node (ref "C3") (pin "2") (pinfunction "2_2") (pintype "passive"))
      (node (ref "C8") (pin "1") (pinfunction "1_1") (pintype "passive"))
      (node (ref "D2") (pin "K") (pinfunction "K_K") (pintype "passive"))
      (node (ref "Q2") (pin "S") (pinfunction "S_S") (pintype "passive"))
      (node (ref "SW1") (pin "3") (pinfunction "3_3") (pintype "passive"))
    )
    (net (code "42") (name "Net-(CN1-Pad1)") (class "Default")
      (node (ref "CN1") (pin "1") (pinfunction "1_1") (pintype "passive"))
      (node (ref "F1") (pin "1") (pinfunction "1_1") (pintype "passive"))
    )
    (net (code "43") (name "Net-(IC1-EN)") (class "Default")
      (node (ref "IC1") (pin "4") (pinfunction "EN_4") (pintype "passive"))
      (node (ref "IC1") (pin "5") (pinfunction "Vin_5") (pintype "passive"))
      (node (ref "L1") (pin "1") (pinfunction "1_1") (pintype "passive"))
      (node (ref "SW1") (pin "1") (pinfunction "1_1") (pintype "passive"))
      (node (ref "SW1") (pin "2") (pinfunction "2_2") (pintype "passive"))
      (node (ref "TP7") (pin "1") (pinfunction "1_1") (pintype "passive"))
    )
    (net (code "44") (name "Net-(IC1-FB)") (class "Default")
      (node (ref "IC1") (pin "3") (pinfunction "FB_3") (pintype "passive"))
      (node (ref "R1") (pin "1") (pinfunction "1_1") (pintype "passive"))
      (node (ref "R3") (pin "2") (pinfunction "2_2") (pintype "passive"))
    )
    (net (code "45") (name "Net-(IC1-SW)") (class "Default")
      (node (ref "D1") (pin "A") (pinfunction "A_A") (pintype "passive"))
      (node (ref "IC1") (pin "1") (pinfunction "SW_1") (pintype "passive"))
      (node (ref "L1") (pin "2") (pinfunction "2_2") (pintype "passive"))
    )
    (net (code "46") (name "Net-(IC3-CE)") (class "Default")
      (node (ref "C2") (pin "2") (pinfunction "2_2") (pintype "passive"))
      (node (ref "C6") (pin "1") (pinfunction "1_1") (pintype "passive"))
      (node (ref "IC3") (pin "4") (pinfunction "Vcc_4") (pintype "passive"))
      (node (ref "IC3") (pin "8") (pinfunction "CE_8") (pintype "passive"))
      (node (ref "R4") (pin "1") (pinfunction "1_1") (pintype "passive"))
    )
    (net (code "47") (name "Net-(IC3-Prog)") (class "Default")
      (node (ref "IC3") (pin "2") (pinfunction "Prog_2") (pintype "passive"))
      (node (ref "R5") (pin "2") (pinfunction "2_2") (pintype "passive"))
    )
    (net (code "48") (name "Net-(IC5-Aisen)") (class "Default")
      (node (ref "IC5") (pin "3") (pinfunction "Aisen_3") (pintype "power_in"))
      (node (ref "IC5") (pin "6") (pinfunction "Bisen_6") (pintype "power_in"))
      (node (ref "R11") (pin "2") (pinfunction "2_2") (pintype "passive"))
    )
    (net (code "49") (name "Net-(IC5-Vint)") (class "Default")
      (node (ref "C14") (pin "1") (pinfunction "1_1") (pintype "passive"))
      (node (ref "IC5") (pin "14") (pinfunction "Vint_14") (pintype "power_in"))
    )
    (net (code "50") (name "Net-(IC6-Aisen)") (class "Default")
      (node (ref "IC6") (pin "3") (pinfunction "Aisen_3") (pintype "power_in"))
      (node (ref "IC6") (pin "6") (pinfunction "Bisen_6") (pintype "power_in"))
      (node (ref "R8") (pin "2") (pinfunction "2_2") (pintype "passive"))
    )
    (net (code "51") (name "Net-(IC6-Aout1)") (class "Default")
      (node (ref "IC6") (pin "2") (pinfunction "Aout1_2") (pintype "passive"))
      (node (ref "IC6") (pin "7") (pinfunction "Bout1_7") (pintype "passive"))
      (node (ref "M_Stroke") (pin "3") (pinfunction "3_3") (pintype "passive"))
      (node (ref "TP6") (pin "1") (pinfunction "1_1") (pintype "passive"))
    )
    (net (code "52") (name "Net-(IC6-Aout2)") (class "Default")
      (node (ref "IC6") (pin "4") (pinfunction "Aout2_4") (pintype "passive"))
      (node (ref "IC6") (pin "5") (pinfunction "Bout2_5") (pintype "passive"))
      (node (ref "M_Stroke") (pin "1") (pinfunction "1_1") (pintype "passive"))
      (node (ref "TP18") (pin "1") (pinfunction "1_1") (pintype "passive"))
    )
    (net (code "53") (name "Net-(IC6-Vint)") (class "Default")
      (node (ref "C20") (pin "1") (pinfunction "1_1") (pintype "passive"))
      (node (ref "IC6") (pin "14") (pinfunction "Vint_14") (pintype "power_in"))
    )
    (net (code "54") (name "Net-(IC8-PB10-I2C2_SCL-USART3_Tx)") (class "Default")
      (node (ref "IC8") (pin "29") (pinfunction "PB10-I2C2_SCL-USART3_Tx_29") (pintype "passive"))
      (node (ref "R19") (pin "2") (pinfunction "2_2") (pintype "passive"))
    )
    (net (code "55") (name "Net-(IC9-CS)") (class "Default")
      (node (ref "IC9") (pin "2") (pinfunction "CS_2") (pintype "passive"))
      (node (ref "R10") (pin "2") (pinfunction "2_2") (pintype "passive"))
    )
    (net (code "56") (name "Net-(IC9-OC)") (class "Default")
      (node (ref "IC9") (pin "3") (pinfunction "OC_3") (pintype "passive"))
      (node (ref "Q3") (pin "5") (pinfunction "G_5") (pintype "passive"))
    )
    (net (code "57") (name "Net-(IC9-OD)") (class "Default")
      (node (ref "IC9") (pin "1") (pinfunction "OD_1") (pintype "passive"))
      (node (ref "Q3") (pin "4") (pinfunction "G_4") (pintype "passive"))
    )
    (net (code "58") (name "Net-(IC9-VCC)") (class "Default")
      (node (ref "C21") (pin "1") (pinfunction "1_1") (pintype "passive"))
      (node (ref "IC9") (pin "5") (pinfunction "VCC_5") (pintype "passive"))
      (node (ref "R9") (pin "2") (pinfunction "2_2") (pintype "passive"))
    )
    (net (code "59") (name "Net-(Q4-PadG)") (class "Default")
      (node (ref "Q4") (pin "G") (pinfunction "G_G") (pintype "passive"))
      (node (ref "R13") (pin "1") (pinfunction "1_1") (pintype "passive"))
      (node (ref "T1") (pin "C") (pinfunction "C_C") (pintype "passive"))
    )
    (net (code "60") (name "Net-(R14-Pad2)") (class "Default")
      (node (ref "R14") (pin "2") (pinfunction "2_2") (pintype "passive"))
      (node (ref "T1") (pin "B") (pinfunction "B_B") (pintype "passive"))
    )
    (net (code "61") (name "Vbat") (class "Default")
      (node (ref "C7") (pin "1") (pinfunction "1_1") (pintype "passive"))
      (node (ref "CN2") (pin "2") (pinfunction "2_2") (pintype "passive"))
      (node (ref "CN2") (pin "3") (pinfunction "3_3") (pintype "passive"))
      (node (ref "IC3") (pin "5") (pinfunction "Bat_5") (pintype "passive"))
      (node (ref "Q2") (pin "D") (pinfunction "D_D") (pintype "passive"))
      (node (ref "R2") (pin "2") (pinfunction "2_2") (pintype "passive"))
      (node (ref "R9") (pin "1") (pinfunction "1_1") (pintype "passive"))
      (node (ref "TP3") (pin "1") (pinfunction "1_1") (pintype "passive"))
    )
    (net (code "62") (name "unconnected-(CN1-Pad3)") (class "Default")
      (node (ref "CN1") (pin "3") (pinfunction "3_3") (pintype "passive"))
    )
    (net (code "63") (name "unconnected-(IC1-NC-Pad6)") (class "Default")
      (node (ref "IC1") (pin "6") (pinfunction "NC_6") (pintype "passive"))
    )
    (net (code "64") (name "unconnected-(IC4-NC-Pad1)") (class "Default")
      (node (ref "IC4") (pin "1") (pinfunction "NC_1") (pintype "passive"))
    )
    (net (code "65") (name "unconnected-(IC5-NC-Pad11)") (class "Default")
      (node (ref "IC5") (pin "11") (pinfunction "NC_11") (pintype "passive"))
    )
    (net (code "66") (name "unconnected-(IC6-NC-Pad11)") (class "Default")
      (node (ref "IC6") (pin "11") (pinfunction "NC_11") (pintype "passive"))
    )
    (net (code "67") (name "unconnected-(IC8-PA3-ADC1-IN3-TIM2_CH4-USART2_Rx-Pad17)") (class "Default")
      (node (ref "IC8") (pin "17") (pinfunction "PA3-ADC1-IN3-TIM2_CH4-USART2_Rx_17") (pintype "passive"))
    )
    (net (code "68") (name "unconnected-(IC8-PA5-SPI1_SCK-ADC1_IN5-DAC2_OUT-Pad21)") (class "Default")
      (node (ref "IC8") (pin "21") (pinfunction "PA5-SPI1_SCK-ADC1_IN5-DAC2_OUT_21") (pintype "passive"))
    )
    (net (code "69") (name "unconnected-(IC8-PA11-TIM1_CH4-Pad44)") (class "Default")
      (node (ref "IC8") (pin "44") (pinfunction "PA11-TIM1_CH4_44") (pintype "passive"))
    )
    (net (code "70") (name "unconnected-(IC8-PA12-Pad45)") (class "Default")
      (node (ref "IC8") (pin "45") (pinfunction "PA12_45") (pintype "passive"))
    )
    (net (code "71") (name "unconnected-(IC8-PA15-SPI1_NSS-Pad50)") (class "Default")
      (node (ref "IC8") (pin "50") (pinfunction "PA15-SPI1_NSS_50") (pintype "passive"))
    )
    (net (code "72") (name "unconnected-(IC8-PB4-NJTRST-SPI1_MISO-Pad56)") (class "Default")
      (node (ref "IC8") (pin "56") (pinfunction "PB4-NJTRST-SPI1_MISO_56") (pintype "passive"))
    )
    (net (code "73") (name "unconnected-(IC8-PB8-TIM4_CH3-Pad61)") (class "Default")
      (node (ref "IC8") (pin "61") (pinfunction "PB8-TIM4_CH3_61") (pintype "passive"))
    )
    (net (code "74") (name "unconnected-(IC8-PB9-TIM4_CH4-Pad62)") (class "Default")
      (node (ref "IC8") (pin "62") (pinfunction "PB9-TIM4_CH4_62") (pintype "passive"))
    )
    (net (code "75") (name "unconnected-(IC8-PB11-I2C2_SDA-USART3_Rx-Pad30)") (class "Default")
      (node (ref "IC8") (pin "30") (pinfunction "PB11-I2C2_SDA-USART3_Rx_30") (pintype "passive"))
    )
    (net (code "76") (name "unconnected-(IC8-PB12-SPI2_NSS-Pad33)") (class "Default")
      (node (ref "IC8") (pin "33") (pinfunction "PB12-SPI2_NSS_33") (pintype "passive"))
    )
    (net (code "77") (name "unconnected-(IC8-PC0-ADC1_IN10-Pad8)") (class "Default")
      (node (ref "IC8") (pin "8") (pinfunction "PC0-ADC1_IN10_8") (pintype "passive"))
    )
    (net (code "78") (name "unconnected-(IC8-PC2-ADC1_IN12-Pad10)") (class "Default")
      (node (ref "IC8") (pin "10") (pinfunction "PC2-ADC1_IN12_10") (pintype "passive"))
    )
    (net (code "79") (name "unconnected-(IC8-PC3-ADC1_IN13-Pad11)") (class "Default")
      (node (ref "IC8") (pin "11") (pinfunction "PC3-ADC1_IN13_11") (pintype "passive"))
    )
    (net (code "80") (name "unconnected-(IC8-PC4-ADC1_IN14-Pad24)") (class "Default")
      (node (ref "IC8") (pin "24") (pinfunction "PC4-ADC1_IN14_24") (pintype "passive"))
    )
    (net (code "81") (name "unconnected-(IC8-PC8-Pad39)") (class "Default")
      (node (ref "IC8") (pin "39") (pinfunction "PC8_39") (pintype "passive"))
    )
    (net (code "82") (name "unconnected-(IC8-PC9-Pad40)") (class "Default")
      (node (ref "IC8") (pin "40") (pinfunction "PC9_40") (pintype "passive"))
    )
    (net (code "83") (name "unconnected-(IC8-PC13-Pad2)") (class "Default")
      (node (ref "IC8") (pin "2") (pinfunction "PC13_2") (pintype "passive"))
    )
    (net (code "84") (name "unconnected-(IC8-PC14-OSC32_IN-Pad3)") (class "Default")
      (node (ref "IC8") (pin "3") (pinfunction "PC14-OSC32_IN_3") (pintype "passive"))
    )
    (net (code "85") (name "unconnected-(IC8-PC15-OSC32_OUT-Pad4)") (class "Default")
      (node (ref "IC8") (pin "4") (pinfunction "PC15-OSC32_OUT_4") (pintype "passive"))
    )
    (net (code "86") (name "unconnected-(IC8-PD0-OSC_IN-Pad5)") (class "Default")
      (node (ref "IC8") (pin "5") (pinfunction "PD0-OSC_IN_5") (pintype "passive"))
    )
    (net (code "87") (name "unconnected-(IC8-PD1-OSC_OUT-Pad6)") (class "Default")
      (node (ref "IC8") (pin "6") (pinfunction "PD1-OSC_OUT_6") (pintype "passive"))
    )
    (net (code "88") (name "unconnected-(IC8-PD2-Pad54)") (class "Default")
      (node (ref "IC8") (pin "54") (pinfunction "PD2_54") (pintype "passive"))
    )
    (net (code "89") (name "unconnected-(IC9-TD-Pad4)") (class "Default")
      (node (ref "IC9") (pin "4") (pinfunction "TD_4") (pintype "passive"))
    )
    (net (code "90") (name "unconnected-(Q3-D-Pad1)") (class "Default")
      (node (ref "Q3") (pin "1") (pinfunction "D_1") (pintype "passive"))
    )
    (net (code "91") (name "unconnected-(Q3-D-Pad8)") (class "Default")
      (node (ref "Q3") (pin "8") (pinfunction "D_8") (pintype "passive"))
    )
  )
)
